# PL_DDR4_SODIMM.net
KiCad netlist of a schematic drawn in Altium Designer
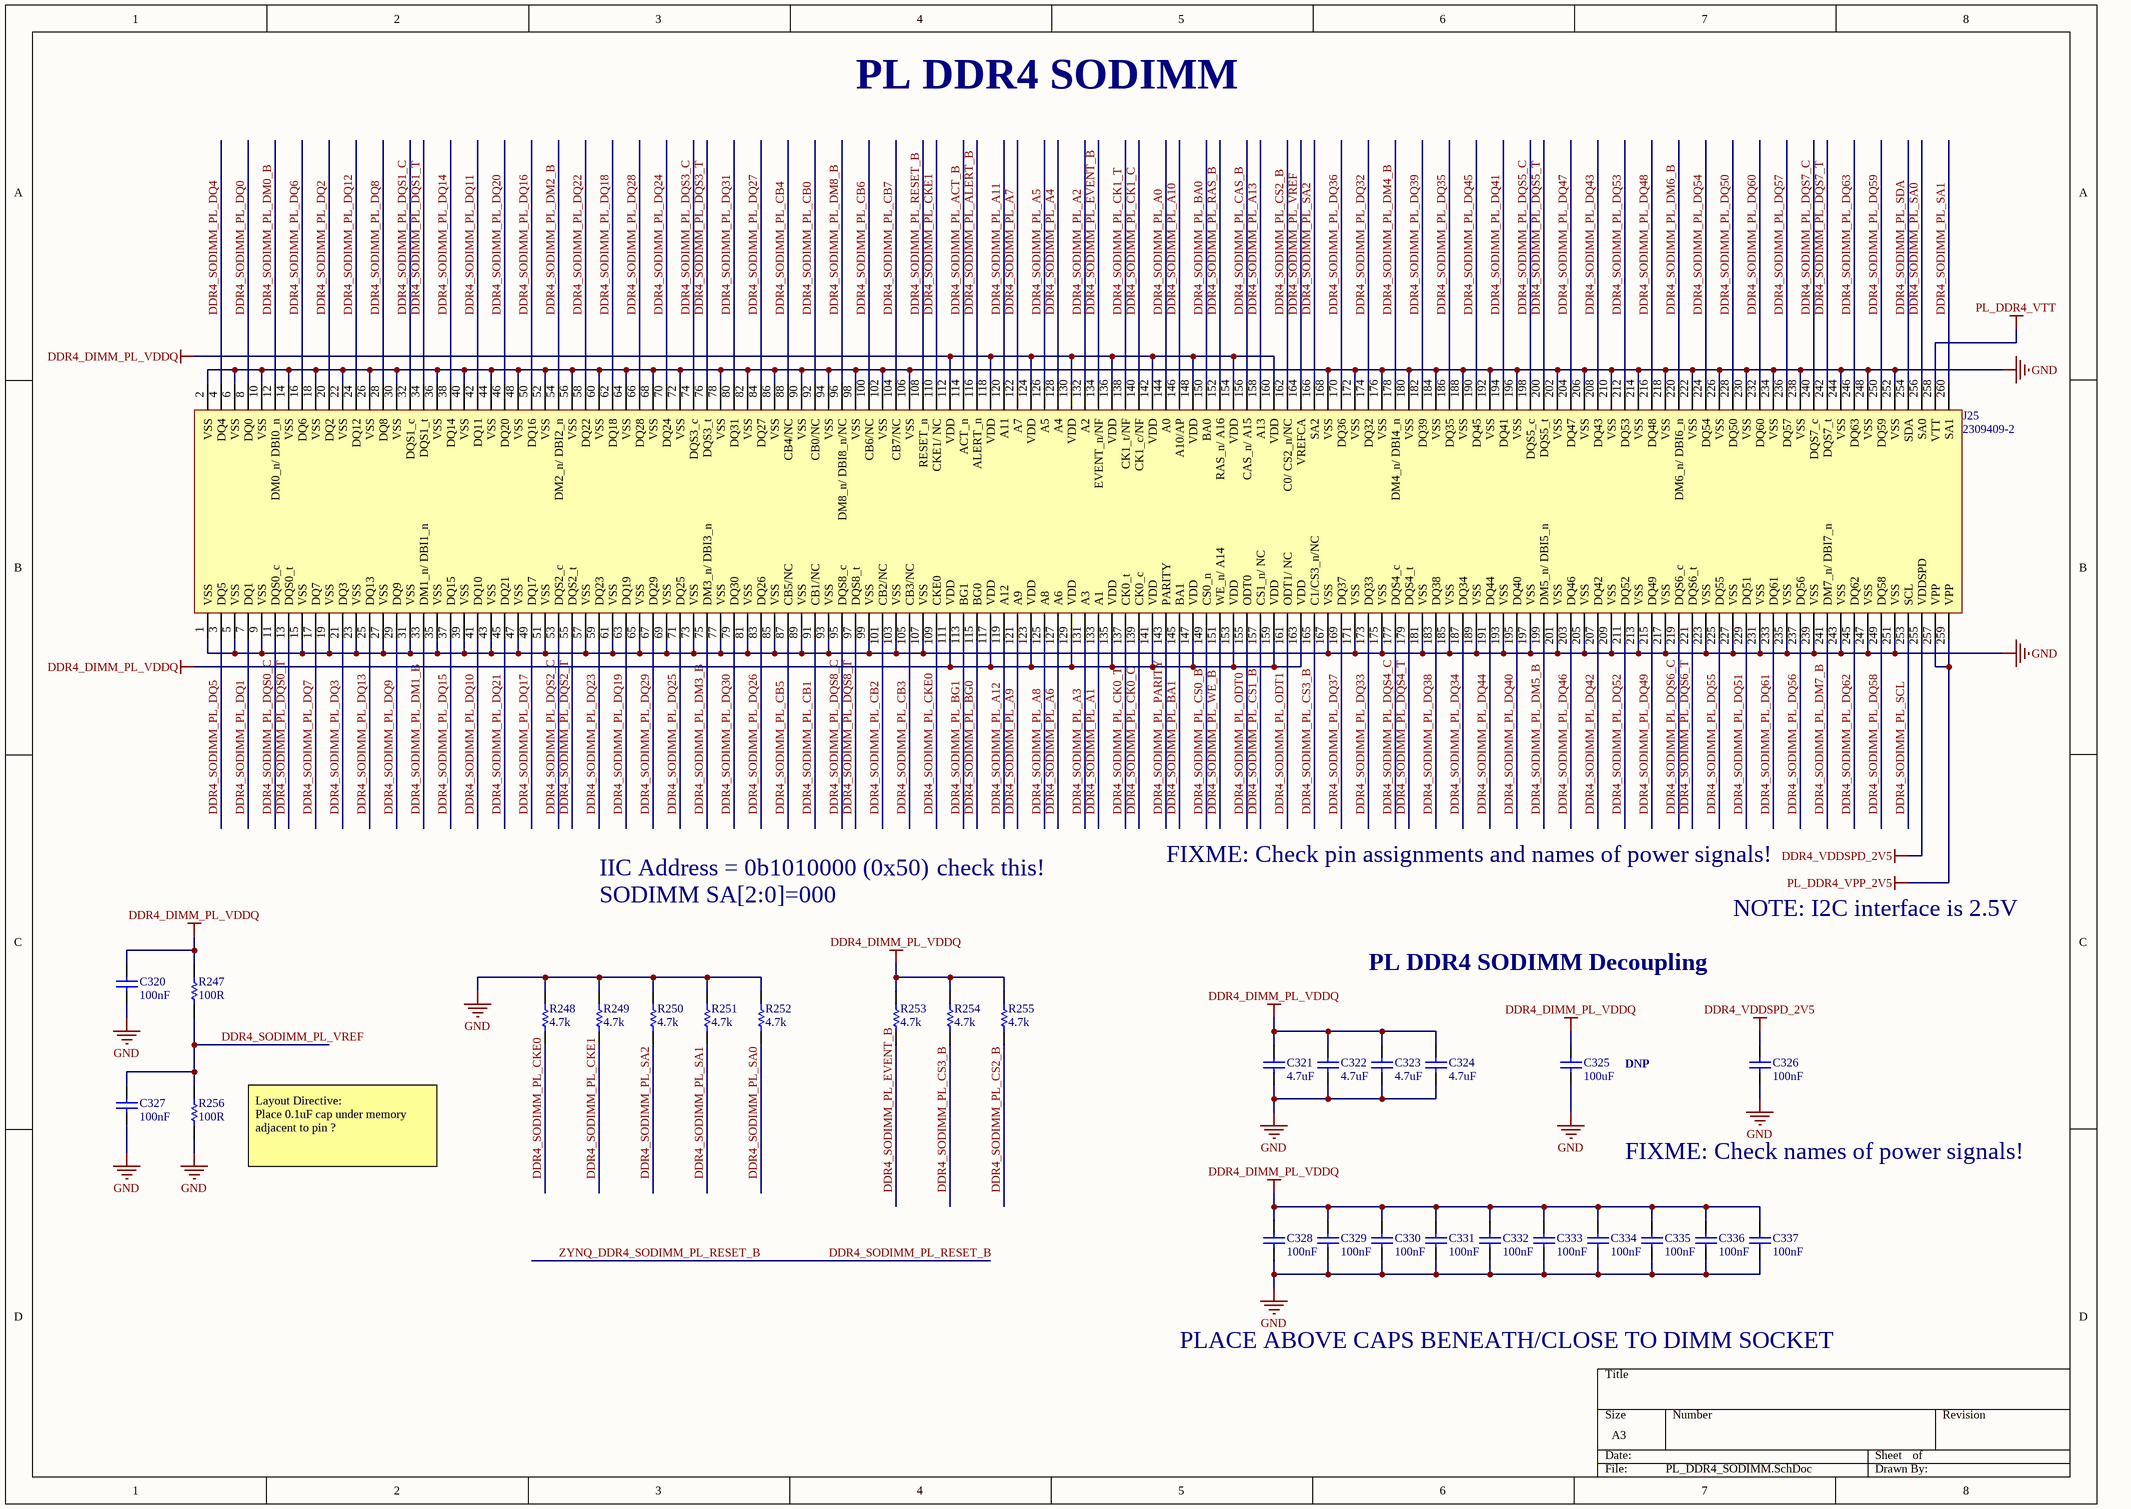
[diagram p0: PL_DDR4_SODIMM.SchDoc]

(export (version "E")
  (design (tool "Eeschema 10.0.6"))
  (components
    (comp (ref "C320")
      (value "100nF")
      (footprint "CAPC1005L_0402")
      (description "CAP CER 0.1UF 25V X7R 0402")
      (fields (field (name "VOLTAGE") "25V") (field (name "TOLERANCE") "10%"))
      (libsource (lib "Ultrascale_SchLib") (part "CAPCER0402X7R100N25V_10T"))
    )
    (comp (ref "C321")
      (value "4.7uF")
      (footprint "CAPC1005L_0402")
      (description "CAP CER 4.7UF 10V X5R 0402")
      (fields (field (name "VOLTAGE") "10V") (field (name "TOLERANCE") "10%"))
      (libsource (lib "Ultrascale_SchLib") (part "CAPCER0402X5R4U710V_10T"))
    )
    (comp (ref "C322")
      (value "4.7uF")
      (footprint "CAPC1005L_0402")
      (description "CAP CER 4.7UF 10V X5R 0402")
      (fields (field (name "VOLTAGE") "10V") (field (name "TOLERANCE") "10%"))
      (libsource (lib "Ultrascale_SchLib") (part "CAPCER0402X5R4U710V_10T"))
    )
    (comp (ref "C323")
      (value "4.7uF")
      (footprint "CAPC1005L_0402")
      (description "CAP CER 4.7UF 10V X5R 0402")
      (fields (field (name "VOLTAGE") "10V") (field (name "TOLERANCE") "10%"))
      (libsource (lib "Ultrascale_SchLib") (part "CAPCER0402X5R4U710V_10T"))
    )
    (comp (ref "C324")
      (value "4.7uF")
      (footprint "CAPC1005L_0402")
      (description "CAP CER 4.7UF 10V X5R 0402")
      (fields (field (name "VOLTAGE") "10V") (field (name "TOLERANCE") "10%"))
      (libsource (lib "Ultrascale_SchLib") (part "CAPCER0402X5R4U710V_10T"))
    )
    (comp (ref "C325")
      (value "100uF")
      (footprint "CAPC3225N_1210")
      (description "CAP CER 100UF 16V X5R 1210")
      (fields (field (name "VOLTAGE") "16V") (field (name "TOLERANCE") "20%"))
      (libsource (lib "Ultrascale_SchLib") (part "CAPCER1210X5R100U16V_20T"))
    )
    (comp (ref "C326")
      (value "100nF")
      (footprint "CAPC1005L_0402")
      (description "CAP CER 0.1UF 25V X7R 0402")
      (fields (field (name "VOLTAGE") "25V") (field (name "TOLERANCE") "10%"))
      (libsource (lib "Ultrascale_SchLib") (part "CAPCER0402X7R100N25V_10T"))
    )
    (comp (ref "C327")
      (value "100nF")
      (footprint "CAPC1005L_0402")
      (description "CAP CER 0.1UF 25V X7R 0402")
      (fields (field (name "VOLTAGE") "25V") (field (name "TOLERANCE") "10%"))
      (libsource (lib "Ultrascale_SchLib") (part "CAPCER0402X7R100N25V_10T"))
    )
    (comp (ref "C328")
      (value "100nF")
      (footprint "CAPC1005L_0402")
      (description "CAP CER 0.1UF 25V X7R 0402")
      (fields (field (name "VOLTAGE") "25V") (field (name "TOLERANCE") "10%"))
      (libsource (lib "Ultrascale_SchLib") (part "CAPCER0402X7R100N25V_10T"))
    )
    (comp (ref "C329")
      (value "100nF")
      (footprint "CAPC1005L_0402")
      (description "CAP CER 0.1UF 25V X7R 0402")
      (fields (field (name "VOLTAGE") "25V") (field (name "TOLERANCE") "10%"))
      (libsource (lib "Ultrascale_SchLib") (part "CAPCER0402X7R100N25V_10T"))
    )
    (comp (ref "C330")
      (value "100nF")
      (footprint "CAPC1005L_0402")
      (description "CAP CER 0.1UF 25V X7R 0402")
      (fields (field (name "VOLTAGE") "25V") (field (name "TOLERANCE") "10%"))
      (libsource (lib "Ultrascale_SchLib") (part "CAPCER0402X7R100N25V_10T"))
    )
    (comp (ref "C331")
      (value "100nF")
      (footprint "CAPC1005L_0402")
      (description "CAP CER 0.1UF 25V X7R 0402")
      (fields (field (name "VOLTAGE") "25V") (field (name "TOLERANCE") "10%"))
      (libsource (lib "Ultrascale_SchLib") (part "CAPCER0402X7R100N25V_10T"))
    )
    (comp (ref "C332")
      (value "100nF")
      (footprint "CAPC1005L_0402")
      (description "CAP CER 0.1UF 25V X7R 0402")
      (fields (field (name "VOLTAGE") "25V") (field (name "TOLERANCE") "10%"))
      (libsource (lib "Ultrascale_SchLib") (part "CAPCER0402X7R100N25V_10T"))
    )
    (comp (ref "C333")
      (value "100nF")
      (footprint "CAPC1005L_0402")
      (description "CAP CER 0.1UF 25V X7R 0402")
      (fields (field (name "VOLTAGE") "25V") (field (name "TOLERANCE") "10%"))
      (libsource (lib "Ultrascale_SchLib") (part "CAPCER0402X7R100N25V_10T"))
    )
    (comp (ref "C334")
      (value "100nF")
      (footprint "CAPC1005L_0402")
      (description "CAP CER 0.1UF 25V X7R 0402")
      (fields (field (name "VOLTAGE") "25V") (field (name "TOLERANCE") "10%"))
      (libsource (lib "Ultrascale_SchLib") (part "CAPCER0402X7R100N25V_10T"))
    )
    (comp (ref "C335")
      (value "100nF")
      (footprint "CAPC1005L_0402")
      (description "CAP CER 0.1UF 25V X7R 0402")
      (fields (field (name "VOLTAGE") "25V") (field (name "TOLERANCE") "10%"))
      (libsource (lib "Ultrascale_SchLib") (part "CAPCER0402X7R100N25V_10T"))
    )
    (comp (ref "C336")
      (value "100nF")
      (footprint "CAPC1005L_0402")
      (description "CAP CER 0.1UF 25V X7R 0402")
      (fields (field (name "VOLTAGE") "25V") (field (name "TOLERANCE") "10%"))
      (libsource (lib "Ultrascale_SchLib") (part "CAPCER0402X7R100N25V_10T"))
    )
    (comp (ref "C337")
      (value "100nF")
      (footprint "CAPC1005L_0402")
      (description "CAP CER 0.1UF 25V X7R 0402")
      (fields (field (name "VOLTAGE") "25V") (field (name "TOLERANCE") "10%"))
      (libsource (lib "Ultrascale_SchLib") (part "CAPCER0402X7R100N25V_10T"))
    )
    (comp (ref "J25")
      (value "2309409-2")
      (footprint "DDR4_SODIMM_MATING")
      (description "DDR4 SODIMM 260P 5.2H STD")
      (libsource (lib "Ultrascale_SchLib") (part "2309409-2"))
    )
    (comp (ref "R247")
      (value "100R")
      (footprint "RESC1005L_0402")
      (description "RES SMD 100 OHM 1% 1/10W 0402")
      (fields (field (name "POWER") "1/10W") (field (name "TOLERANCE") "1%"))
      (libsource (lib "Ultrascale_SchLib") (part "RES0402_100R_0W1_1T"))
    )
    (comp (ref "R248")
      (value "4.7k")
      (footprint "RESC1005L_0402")
      (description "RES SMD 4.7K OHM 1% 1/10W 0402")
      (fields (field (name "POWER") "1/10W") (field (name "TOLERANCE") "1%"))
      (libsource (lib "Ultrascale_SchLib") (part "RES0402_4K7_0W1_1T"))
    )
    (comp (ref "R249")
      (value "4.7k")
      (footprint "RESC1005L_0402")
      (description "RES SMD 4.7K OHM 1% 1/10W 0402")
      (fields (field (name "POWER") "1/10W") (field (name "TOLERANCE") "1%"))
      (libsource (lib "Ultrascale_SchLib") (part "RES0402_4K7_0W1_1T"))
    )
    (comp (ref "R250")
      (value "4.7k")
      (footprint "RESC1005L_0402")
      (description "RES SMD 4.7K OHM 1% 1/10W 0402")
      (fields (field (name "POWER") "1/10W") (field (name "TOLERANCE") "1%"))
      (libsource (lib "Ultrascale_SchLib") (part "RES0402_4K7_0W1_1T"))
    )
    (comp (ref "R251")
      (value "4.7k")
      (footprint "RESC1005L_0402")
      (description "RES SMD 4.7K OHM 1% 1/10W 0402")
      (fields (field (name "POWER") "1/10W") (field (name "TOLERANCE") "1%"))
      (libsource (lib "Ultrascale_SchLib") (part "RES0402_4K7_0W1_1T"))
    )
    (comp (ref "R252")
      (value "4.7k")
      (footprint "RESC1005L_0402")
      (description "RES SMD 4.7K OHM 1% 1/10W 0402")
      (fields (field (name "POWER") "1/10W") (field (name "TOLERANCE") "1%"))
      (libsource (lib "Ultrascale_SchLib") (part "RES0402_4K7_0W1_1T"))
    )
    (comp (ref "R253")
      (value "4.7k")
      (footprint "RESC1005L_0402")
      (description "RES SMD 4.7K OHM 1% 1/10W 0402")
      (fields (field (name "POWER") "1/10W") (field (name "TOLERANCE") "1%"))
      (libsource (lib "Ultrascale_SchLib") (part "RES0402_4K7_0W1_1T"))
    )
    (comp (ref "R254")
      (value "4.7k")
      (footprint "RESC1005L_0402")
      (description "RES SMD 4.7K OHM 1% 1/10W 0402")
      (fields (field (name "POWER") "1/10W") (field (name "TOLERANCE") "1%"))
      (libsource (lib "Ultrascale_SchLib") (part "RES0402_4K7_0W1_1T"))
    )
    (comp (ref "R255")
      (value "4.7k")
      (footprint "RESC1005L_0402")
      (description "RES SMD 4.7K OHM 1% 1/10W 0402")
      (fields (field (name "POWER") "1/10W") (field (name "TOLERANCE") "1%"))
      (libsource (lib "Ultrascale_SchLib") (part "RES0402_4K7_0W1_1T"))
    )
    (comp (ref "R256")
      (value "100R")
      (footprint "RESC1005L_0402")
      (description "RES SMD 100 OHM 1% 1/10W 0402")
      (fields (field (name "POWER") "1/10W") (field (name "TOLERANCE") "1%"))
      (libsource (lib "Ultrascale_SchLib") (part "RES0402_100R_0W1_1T"))
    )
  )
  (nets
    (net (code "1") (name "/DDR4_SODIMM_PL_A0") (class "Default")
      (node (ref "J25") (pin "144") (pinfunction "A0_144") (pintype "power_in"))
    )
    (net (code "2") (name "/DDR4_SODIMM_PL_A1") (class "Default")
      (node (ref "J25") (pin "133") (pinfunction "A1_133") (pintype "power_in"))
    )
    (net (code "3") (name "/DDR4_SODIMM_PL_A2") (class "Default")
      (node (ref "J25") (pin "132") (pinfunction "A2_132") (pintype "power_in"))
    )
    (net (code "4") (name "/DDR4_SODIMM_PL_A3") (class "Default")
      (node (ref "J25") (pin "131") (pinfunction "A3_131") (pintype "power_in"))
    )
    (net (code "5") (name "/DDR4_SODIMM_PL_A4") (class "Default")
      (node (ref "J25") (pin "128") (pinfunction "A4_128") (pintype "power_in"))
    )
    (net (code "6") (name "/DDR4_SODIMM_PL_A5") (class "Default")
      (node (ref "J25") (pin "126") (pinfunction "A5_126") (pintype "power_in"))
    )
    (net (code "7") (name "/DDR4_SODIMM_PL_A6") (class "Default")
      (node (ref "J25") (pin "127") (pinfunction "A6_127") (pintype "power_in"))
    )
    (net (code "8") (name "/DDR4_SODIMM_PL_A7") (class "Default")
      (node (ref "J25") (pin "122") (pinfunction "A7_122") (pintype "power_in"))
    )
    (net (code "9") (name "/DDR4_SODIMM_PL_A8") (class "Default")
      (node (ref "J25") (pin "125") (pinfunction "A8_125") (pintype "power_in"))
    )
    (net (code "10") (name "/DDR4_SODIMM_PL_A9") (class "Default")
      (node (ref "J25") (pin "121") (pinfunction "A9_121") (pintype "power_in"))
    )
    (net (code "11") (name "/DDR4_SODIMM_PL_A10") (class "Default")
      (node (ref "J25") (pin "146") (pinfunction "A10/AP_146") (pintype "power_in"))
    )
    (net (code "12") (name "/DDR4_SODIMM_PL_A11") (class "Default")
      (node (ref "J25") (pin "120") (pinfunction "A11_120") (pintype "power_in"))
    )
    (net (code "13") (name "/DDR4_SODIMM_PL_A12") (class "Default")
      (node (ref "J25") (pin "119") (pinfunction "A12_119") (pintype "power_in"))
    )
    (net (code "14") (name "/DDR4_SODIMM_PL_A13") (class "Default")
      (node (ref "J25") (pin "158") (pinfunction "A13_158") (pintype "power_in"))
    )
    (net (code "15") (name "/DDR4_SODIMM_PL_ACT_B") (class "Default")
      (node (ref "J25") (pin "114") (pinfunction "ACT_n_114") (pintype "power_in"))
    )
    (net (code "16") (name "/DDR4_SODIMM_PL_ALERT_B") (class "Default")
      (node (ref "J25") (pin "116") (pinfunction "ALERT_n_116") (pintype "power_in"))
    )
    (net (code "17") (name "/DDR4_SODIMM_PL_BA0") (class "Default")
      (node (ref "J25") (pin "150") (pinfunction "BA0_150") (pintype "power_in"))
    )
    (net (code "18") (name "/DDR4_SODIMM_PL_BA1") (class "Default")
      (node (ref "J25") (pin "145") (pinfunction "BA1_145") (pintype "power_in"))
    )
    (net (code "19") (name "/DDR4_SODIMM_PL_BG0") (class "Default")
      (node (ref "J25") (pin "115") (pinfunction "BG0_115") (pintype "power_in"))
    )
    (net (code "20") (name "/DDR4_SODIMM_PL_BG1") (class "Default")
      (node (ref "J25") (pin "113") (pinfunction "BG1_113") (pintype "power_in"))
    )
    (net (code "21") (name "/DDR4_SODIMM_PL_CAS_B") (class "Default")
      (node (ref "J25") (pin "156") (pinfunction "CAS_n/_A15_156") (pintype "power_in"))
    )
    (net (code "22") (name "/DDR4_SODIMM_PL_CB0") (class "Default")
      (node (ref "J25") (pin "92") (pinfunction "CB0/NC_92") (pintype "power_in"))
    )
    (net (code "23") (name "/DDR4_SODIMM_PL_CB1") (class "Default")
      (node (ref "J25") (pin "91") (pinfunction "CB1/NC_91") (pintype "power_in"))
    )
    (net (code "24") (name "/DDR4_SODIMM_PL_CB2") (class "Default")
      (node (ref "J25") (pin "101") (pinfunction "CB2/NC_101") (pintype "power_in"))
    )
    (net (code "25") (name "/DDR4_SODIMM_PL_CB3") (class "Default")
      (node (ref "J25") (pin "105") (pinfunction "CB3/NC_105") (pintype "power_in"))
    )
    (net (code "26") (name "/DDR4_SODIMM_PL_CB4") (class "Default")
      (node (ref "J25") (pin "88") (pinfunction "CB4/NC_88") (pintype "power_in"))
    )
    (net (code "27") (name "/DDR4_SODIMM_PL_CB5") (class "Default")
      (node (ref "J25") (pin "87") (pinfunction "CB5/NC_87") (pintype "power_in"))
    )
    (net (code "28") (name "/DDR4_SODIMM_PL_CB6") (class "Default")
      (node (ref "J25") (pin "100") (pinfunction "CB6/NC_100") (pintype "power_in"))
    )
    (net (code "29") (name "/DDR4_SODIMM_PL_CB7") (class "Default")
      (node (ref "J25") (pin "104") (pinfunction "CB7/NC_104") (pintype "power_in"))
    )
    (net (code "30") (name "/DDR4_SODIMM_PL_CK0_C") (class "Default")
      (node (ref "J25") (pin "139") (pinfunction "CK0_c_139") (pintype "power_in"))
    )
    (net (code "31") (name "/DDR4_SODIMM_PL_CK0_T") (class "Default")
      (node (ref "J25") (pin "137") (pinfunction "CK0_t_137") (pintype "power_in"))
    )
    (net (code "32") (name "/DDR4_SODIMM_PL_CK1_C") (class "Default")
      (node (ref "J25") (pin "140") (pinfunction "CK1_c/NF_140") (pintype "power_in"))
    )
    (net (code "33") (name "/DDR4_SODIMM_PL_CK1_T") (class "Default")
      (node (ref "J25") (pin "138") (pinfunction "CK1_t/NF_138") (pintype "power_in"))
    )
    (net (code "34") (name "/DDR4_SODIMM_PL_CKE0") (class "Default")
      (node (ref "J25") (pin "109") (pinfunction "CKE0_109") (pintype "power_in"))
      (node (ref "R248") (pin "1") (pinfunction "1_1") (pintype "passive"))
    )
    (net (code "35") (name "/DDR4_SODIMM_PL_CKE1") (class "Default")
      (node (ref "J25") (pin "110") (pinfunction "CKE1/_NC_110") (pintype "power_in"))
      (node (ref "R249") (pin "1") (pinfunction "1_1") (pintype "passive"))
    )
    (net (code "36") (name "/DDR4_SODIMM_PL_CS0_B") (class "Default")
      (node (ref "J25") (pin "149") (pinfunction "CS0_n_149") (pintype "power_in"))
    )
    (net (code "37") (name "/DDR4_SODIMM_PL_CS1_B") (class "Default")
      (node (ref "J25") (pin "157") (pinfunction "CS1_n/_NC_157") (pintype "power_in"))
    )
    (net (code "38") (name "/DDR4_SODIMM_PL_CS2_B") (class "Default")
      (node (ref "J25") (pin "162") (pinfunction "C0/_CS2_n/NC_162") (pintype "power_in"))
      (node (ref "R255") (pin "1") (pinfunction "1_1") (pintype "passive"))
    )
    (net (code "39") (name "/DDR4_SODIMM_PL_CS3_B") (class "Default")
      (node (ref "J25") (pin "165") (pinfunction "C1/CS3_n/NC_165") (pintype "power_in"))
      (node (ref "R254") (pin "1") (pinfunction "1_1") (pintype "passive"))
    )
    (net (code "40") (name "/DDR4_SODIMM_PL_DM0_B") (class "Default")
      (node (ref "J25") (pin "12") (pinfunction "DM0_n/_DBI0_n_12") (pintype "power_in"))
    )
    (net (code "41") (name "/DDR4_SODIMM_PL_DM1_B") (class "Default")
      (node (ref "J25") (pin "33") (pinfunction "DM1_n/_DBI1_n_33") (pintype "power_in"))
    )
    (net (code "42") (name "/DDR4_SODIMM_PL_DM2_B") (class "Default")
      (node (ref "J25") (pin "54") (pinfunction "DM2_n/_DBI2_n_54") (pintype "power_in"))
    )
    (net (code "43") (name "/DDR4_SODIMM_PL_DM3_B") (class "Default")
      (node (ref "J25") (pin "75") (pinfunction "DM3_n/_DBI3_n_75") (pintype "power_in"))
    )
    (net (code "44") (name "/DDR4_SODIMM_PL_DM4_B") (class "Default")
      (node (ref "J25") (pin "178") (pinfunction "DM4_n/_DBI4_n_178") (pintype "power_in"))
    )
    (net (code "45") (name "/DDR4_SODIMM_PL_DM5_B") (class "Default")
      (node (ref "J25") (pin "199") (pinfunction "DM5_n/_DBI5_n_199") (pintype "power_in"))
    )
    (net (code "46") (name "/DDR4_SODIMM_PL_DM6_B") (class "Default")
      (node (ref "J25") (pin "220") (pinfunction "DM6_n/_DBI6_n_220") (pintype "power_in"))
    )
    (net (code "47") (name "/DDR4_SODIMM_PL_DM7_B") (class "Default")
      (node (ref "J25") (pin "241") (pinfunction "DM7_n/_DBI7_n_241") (pintype "power_in"))
    )
    (net (code "48") (name "/DDR4_SODIMM_PL_DM8_B") (class "Default")
      (node (ref "J25") (pin "96") (pinfunction "DM8_n/_DBI8_n/NC_96") (pintype "power_in"))
    )
    (net (code "49") (name "/DDR4_SODIMM_PL_DQ0") (class "Default")
      (node (ref "J25") (pin "8") (pinfunction "DQ0_8") (pintype "power_in"))
    )
    (net (code "50") (name "/DDR4_SODIMM_PL_DQ1") (class "Default")
      (node (ref "J25") (pin "7") (pinfunction "DQ1_7") (pintype "power_in"))
    )
    (net (code "51") (name "/DDR4_SODIMM_PL_DQ2") (class "Default")
      (node (ref "J25") (pin "20") (pinfunction "DQ2_20") (pintype "power_in"))
    )
    (net (code "52") (name "/DDR4_SODIMM_PL_DQ3") (class "Default")
      (node (ref "J25") (pin "21") (pinfunction "DQ3_21") (pintype "power_in"))
    )
    (net (code "53") (name "/DDR4_SODIMM_PL_DQ4") (class "Default")
      (node (ref "J25") (pin "4") (pinfunction "DQ4_4") (pintype "power_in"))
    )
    (net (code "54") (name "/DDR4_SODIMM_PL_DQ5") (class "Default")
      (node (ref "J25") (pin "3") (pinfunction "DQ5_3") (pintype "power_in"))
    )
    (net (code "55") (name "/DDR4_SODIMM_PL_DQ6") (class "Default")
      (node (ref "J25") (pin "16") (pinfunction "DQ6_16") (pintype "power_in"))
    )
    (net (code "56") (name "/DDR4_SODIMM_PL_DQ7") (class "Default")
      (node (ref "J25") (pin "17") (pinfunction "DQ7_17") (pintype "power_in"))
    )
    (net (code "57") (name "/DDR4_SODIMM_PL_DQ8") (class "Default")
      (node (ref "J25") (pin "28") (pinfunction "DQ8_28") (pintype "power_in"))
    )
    (net (code "58") (name "/DDR4_SODIMM_PL_DQ9") (class "Default")
      (node (ref "J25") (pin "29") (pinfunction "DQ9_29") (pintype "power_in"))
    )
    (net (code "59") (name "/DDR4_SODIMM_PL_DQ10") (class "Default")
      (node (ref "J25") (pin "41") (pinfunction "DQ10_41") (pintype "power_in"))
    )
    (net (code "60") (name "/DDR4_SODIMM_PL_DQ11") (class "Default")
      (node (ref "J25") (pin "42") (pinfunction "DQ11_42") (pintype "power_in"))
    )
    (net (code "61") (name "/DDR4_SODIMM_PL_DQ12") (class "Default")
      (node (ref "J25") (pin "24") (pinfunction "DQ12_24") (pintype "power_in"))
    )
    (net (code "62") (name "/DDR4_SODIMM_PL_DQ13") (class "Default")
      (node (ref "J25") (pin "25") (pinfunction "DQ13_25") (pintype "power_in"))
    )
    (net (code "63") (name "/DDR4_SODIMM_PL_DQ14") (class "Default")
      (node (ref "J25") (pin "38") (pinfunction "DQ14_38") (pintype "power_in"))
    )
    (net (code "64") (name "/DDR4_SODIMM_PL_DQ15") (class "Default")
      (node (ref "J25") (pin "37") (pinfunction "DQ15_37") (pintype "power_in"))
    )
    (net (code "65") (name "/DDR4_SODIMM_PL_DQ16") (class "Default")
      (node (ref "J25") (pin "50") (pinfunction "DQ16_50") (pintype "power_in"))
    )
    (net (code "66") (name "/DDR4_SODIMM_PL_DQ17") (class "Default")
      (node (ref "J25") (pin "49") (pinfunction "DQ17_49") (pintype "power_in"))
    )
    (net (code "67") (name "/DDR4_SODIMM_PL_DQ18") (class "Default")
      (node (ref "J25") (pin "62") (pinfunction "DQ18_62") (pintype "power_in"))
    )
    (net (code "68") (name "/DDR4_SODIMM_PL_DQ19") (class "Default")
      (node (ref "J25") (pin "63") (pinfunction "DQ19_63") (pintype "power_in"))
    )
    (net (code "69") (name "/DDR4_SODIMM_PL_DQ20") (class "Default")
      (node (ref "J25") (pin "46") (pinfunction "DQ20_46") (pintype "power_in"))
    )
    (net (code "70") (name "/DDR4_SODIMM_PL_DQ21") (class "Default")
      (node (ref "J25") (pin "45") (pinfunction "DQ21_45") (pintype "power_in"))
    )
    (net (code "71") (name "/DDR4_SODIMM_PL_DQ22") (class "Default")
      (node (ref "J25") (pin "58") (pinfunction "DQ22_58") (pintype "power_in"))
    )
    (net (code "72") (name "/DDR4_SODIMM_PL_DQ23") (class "Default")
      (node (ref "J25") (pin "59") (pinfunction "DQ23_59") (pintype "power_in"))
    )
    (net (code "73") (name "/DDR4_SODIMM_PL_DQ24") (class "Default")
      (node (ref "J25") (pin "70") (pinfunction "DQ24_70") (pintype "power_in"))
    )
    (net (code "74") (name "/DDR4_SODIMM_PL_DQ25") (class "Default")
      (node (ref "J25") (pin "71") (pinfunction "DQ25_71") (pintype "power_in"))
    )
    (net (code "75") (name "/DDR4_SODIMM_PL_DQ26") (class "Default")
      (node (ref "J25") (pin "83") (pinfunction "DQ26_83") (pintype "power_in"))
    )
    (net (code "76") (name "/DDR4_SODIMM_PL_DQ27") (class "Default")
      (node (ref "J25") (pin "84") (pinfunction "DQ27_84") (pintype "power_in"))
    )
    (net (code "77") (name "/DDR4_SODIMM_PL_DQ28") (class "Default")
      (node (ref "J25") (pin "66") (pinfunction "DQ28_66") (pintype "power_in"))
    )
    (net (code "78") (name "/DDR4_SODIMM_PL_DQ29") (class "Default")
      (node (ref "J25") (pin "67") (pinfunction "DQ29_67") (pintype "power_in"))
    )
    (net (code "79") (name "/DDR4_SODIMM_PL_DQ30") (class "Default")
      (node (ref "J25") (pin "79") (pinfunction "DQ30_79") (pintype "power_in"))
    )
    (net (code "80") (name "/DDR4_SODIMM_PL_DQ31") (class "Default")
      (node (ref "J25") (pin "80") (pinfunction "DQ31_80") (pintype "power_in"))
    )
    (net (code "81") (name "/DDR4_SODIMM_PL_DQ32") (class "Default")
      (node (ref "J25") (pin "174") (pinfunction "DQ32_174") (pintype "power_in"))
    )
    (net (code "82") (name "/DDR4_SODIMM_PL_DQ33") (class "Default")
      (node (ref "J25") (pin "173") (pinfunction "DQ33_173") (pintype "power_in"))
    )
    (net (code "83") (name "/DDR4_SODIMM_PL_DQ34") (class "Default")
      (node (ref "J25") (pin "187") (pinfunction "DQ34_187") (pintype "power_in"))
    )
    (net (code "84") (name "/DDR4_SODIMM_PL_DQ35") (class "Default")
      (node (ref "J25") (pin "186") (pinfunction "DQ35_186") (pintype "power_in"))
    )
    (net (code "85") (name "/DDR4_SODIMM_PL_DQ36") (class "Default")
      (node (ref "J25") (pin "170") (pinfunction "DQ36_170") (pintype "power_in"))
    )
    (net (code "86") (name "/DDR4_SODIMM_PL_DQ37") (class "Default")
      (node (ref "J25") (pin "169") (pinfunction "DQ37_169") (pintype "power_in"))
    )
    (net (code "87") (name "/DDR4_SODIMM_PL_DQ38") (class "Default")
      (node (ref "J25") (pin "183") (pinfunction "DQ38_183") (pintype "power_in"))
    )
    (net (code "88") (name "/DDR4_SODIMM_PL_DQ39") (class "Default")
      (node (ref "J25") (pin "182") (pinfunction "DQ39_182") (pintype "power_in"))
    )
    (net (code "89") (name "/DDR4_SODIMM_PL_DQ40") (class "Default")
      (node (ref "J25") (pin "195") (pinfunction "DQ40_195") (pintype "power_in"))
    )
    (net (code "90") (name "/DDR4_SODIMM_PL_DQ41") (class "Default")
      (node (ref "J25") (pin "194") (pinfunction "DQ41_194") (pintype "power_in"))
    )
    (net (code "91") (name "/DDR4_SODIMM_PL_DQ42") (class "Default")
      (node (ref "J25") (pin "207") (pinfunction "DQ42_207") (pintype "power_in"))
    )
    (net (code "92") (name "/DDR4_SODIMM_PL_DQ43") (class "Default")
      (node (ref "J25") (pin "208") (pinfunction "DQ43_208") (pintype "power_in"))
    )
    (net (code "93") (name "/DDR4_SODIMM_PL_DQ44") (class "Default")
      (node (ref "J25") (pin "191") (pinfunction "DQ44_191") (pintype "power_in"))
    )
    (net (code "94") (name "/DDR4_SODIMM_PL_DQ45") (class "Default")
      (node (ref "J25") (pin "190") (pinfunction "DQ45_190") (pintype "power_in"))
    )
    (net (code "95") (name "/DDR4_SODIMM_PL_DQ46") (class "Default")
      (node (ref "J25") (pin "203") (pinfunction "DQ46_203") (pintype "power_in"))
    )
    (net (code "96") (name "/DDR4_SODIMM_PL_DQ47") (class "Default")
      (node (ref "J25") (pin "204") (pinfunction "DQ47_204") (pintype "power_in"))
    )
    (net (code "97") (name "/DDR4_SODIMM_PL_DQ48") (class "Default")
      (node (ref "J25") (pin "216") (pinfunction "DQ48_216") (pintype "power_in"))
    )
    (net (code "98") (name "/DDR4_SODIMM_PL_DQ49") (class "Default")
      (node (ref "J25") (pin "215") (pinfunction "DQ49_215") (pintype "power_in"))
    )
    (net (code "99") (name "/DDR4_SODIMM_PL_DQ50") (class "Default")
      (node (ref "J25") (pin "228") (pinfunction "DQ50_228") (pintype "power_in"))
    )
    (net (code "100") (name "/DDR4_SODIMM_PL_DQ51") (class "Default")
      (node (ref "J25") (pin "229") (pinfunction "DQ51_229") (pintype "power_in"))
    )
    (net (code "101") (name "/DDR4_SODIMM_PL_DQ52") (class "Default")
      (node (ref "J25") (pin "211") (pinfunction "DQ52_211") (pintype "power_in"))
    )
    (net (code "102") (name "/DDR4_SODIMM_PL_DQ53") (class "Default")
      (node (ref "J25") (pin "212") (pinfunction "DQ53_212") (pintype "power_in"))
    )
    (net (code "103") (name "/DDR4_SODIMM_PL_DQ54") (class "Default")
      (node (ref "J25") (pin "224") (pinfunction "DQ54_224") (pintype "power_in"))
    )
    (net (code "104") (name "/DDR4_SODIMM_PL_DQ55") (class "Default")
      (node (ref "J25") (pin "225") (pinfunction "DQ55_225") (pintype "power_in"))
    )
    (net (code "105") (name "/DDR4_SODIMM_PL_DQ56") (class "Default")
      (node (ref "J25") (pin "237") (pinfunction "DQ56_237") (pintype "power_in"))
    )
    (net (code "106") (name "/DDR4_SODIMM_PL_DQ57") (class "Default")
      (node (ref "J25") (pin "236") (pinfunction "DQ57_236") (pintype "power_in"))
    )
    (net (code "107") (name "/DDR4_SODIMM_PL_DQ58") (class "Default")
      (node (ref "J25") (pin "249") (pinfunction "DQ58_249") (pintype "power_in"))
    )
    (net (code "108") (name "/DDR4_SODIMM_PL_DQ59") (class "Default")
      (node (ref "J25") (pin "250") (pinfunction "DQ59_250") (pintype "power_in"))
    )
    (net (code "109") (name "/DDR4_SODIMM_PL_DQ60") (class "Default")
      (node (ref "J25") (pin "232") (pinfunction "DQ60_232") (pintype "power_in"))
    )
    (net (code "110") (name "/DDR4_SODIMM_PL_DQ61") (class "Default")
      (node (ref "J25") (pin "233") (pinfunction "DQ61_233") (pintype "power_in"))
    )
    (net (code "111") (name "/DDR4_SODIMM_PL_DQ62") (class "Default")
      (node (ref "J25") (pin "245") (pinfunction "DQ62_245") (pintype "power_in"))
    )
    (net (code "112") (name "/DDR4_SODIMM_PL_DQ63") (class "Default")
      (node (ref "J25") (pin "246") (pinfunction "DQ63_246") (pintype "power_in"))
    )
    (net (code "113") (name "/DDR4_SODIMM_PL_DQS0_C") (class "Default")
      (node (ref "J25") (pin "11") (pinfunction "DQS0_c_11") (pintype "power_in"))
    )
    (net (code "114") (name "/DDR4_SODIMM_PL_DQS0_T") (class "Default")
      (node (ref "J25") (pin "13") (pinfunction "DQS0_t_13") (pintype "power_in"))
    )
    (net (code "115") (name "/DDR4_SODIMM_PL_DQS1_C") (class "Default")
      (node (ref "J25") (pin "32") (pinfunction "DQS1_c_32") (pintype "power_in"))
    )
    (net (code "116") (name "/DDR4_SODIMM_PL_DQS1_T") (class "Default")
      (node (ref "J25") (pin "34") (pinfunction "DQS1_t_34") (pintype "power_in"))
    )
    (net (code "117") (name "/DDR4_SODIMM_PL_DQS2_C") (class "Default")
      (node (ref "J25") (pin "53") (pinfunction "DQS2_c_53") (pintype "power_in"))
    )
    (net (code "118") (name "/DDR4_SODIMM_PL_DQS2_T") (class "Default")
      (node (ref "J25") (pin "55") (pinfunction "DQS2_t_55") (pintype "power_in"))
    )
    (net (code "119") (name "/DDR4_SODIMM_PL_DQS3_C") (class "Default")
      (node (ref "J25") (pin "74") (pinfunction "DQS3_c_74") (pintype "power_in"))
    )
    (net (code "120") (name "/DDR4_SODIMM_PL_DQS3_T") (class "Default")
      (node (ref "J25") (pin "76") (pinfunction "DQS3_t_76") (pintype "power_in"))
    )
    (net (code "121") (name "/DDR4_SODIMM_PL_DQS4_C") (class "Default")
      (node (ref "J25") (pin "177") (pinfunction "DQS4_c_177") (pintype "power_in"))
    )
    (net (code "122") (name "/DDR4_SODIMM_PL_DQS4_T") (class "Default")
      (node (ref "J25") (pin "179") (pinfunction "DQS4_t_179") (pintype "power_in"))
    )
    (net (code "123") (name "/DDR4_SODIMM_PL_DQS5_C") (class "Default")
      (node (ref "J25") (pin "198") (pinfunction "DQS5_c_198") (pintype "power_in"))
    )
    (net (code "124") (name "/DDR4_SODIMM_PL_DQS5_T") (class "Default")
      (node (ref "J25") (pin "200") (pinfunction "DQS5_t_200") (pintype "power_in"))
    )
    (net (code "125") (name "/DDR4_SODIMM_PL_DQS6_C") (class "Default")
      (node (ref "J25") (pin "219") (pinfunction "DQS6_c_219") (pintype "power_in"))
    )
    (net (code "126") (name "/DDR4_SODIMM_PL_DQS6_T") (class "Default")
      (node (ref "J25") (pin "221") (pinfunction "DQS6_t_221") (pintype "power_in"))
    )
    (net (code "127") (name "/DDR4_SODIMM_PL_DQS7_C") (class "Default")
      (node (ref "J25") (pin "240") (pinfunction "DQS7_c_240") (pintype "power_in"))
    )
    (net (code "128") (name "/DDR4_SODIMM_PL_DQS7_T") (class "Default")
      (node (ref "J25") (pin "242") (pinfunction "DQS7_t_242") (pintype "power_in"))
    )
    (net (code "129") (name "/DDR4_SODIMM_PL_DQS8_C") (class "Default")
      (node (ref "J25") (pin "95") (pinfunction "DQS8_c_95") (pintype "power_in"))
    )
    (net (code "130") (name "/DDR4_SODIMM_PL_DQS8_T") (class "Default")
      (node (ref "J25") (pin "97") (pinfunction "DQS8_t_97") (pintype "power_in"))
    )
    (net (code "131") (name "/DDR4_SODIMM_PL_EVENT_B") (class "Default")
      (node (ref "J25") (pin "134") (pinfunction "EVENT_n/NF_134") (pintype "power_in"))
      (node (ref "R253") (pin "1") (pinfunction "1_1") (pintype "passive"))
    )
    (net (code "132") (name "/DDR4_SODIMM_PL_ODT0") (class "Default")
      (node (ref "J25") (pin "155") (pinfunction "ODT0_155") (pintype "power_in"))
    )
    (net (code "133") (name "/DDR4_SODIMM_PL_ODT1") (class "Default")
      (node (ref "J25") (pin "161") (pinfunction "ODT1/_NC_161") (pintype "power_in"))
    )
    (net (code "134") (name "/DDR4_SODIMM_PL_PARITY") (class "Default")
      (node (ref "J25") (pin "143") (pinfunction "PARITY_143") (pintype "power_in"))
    )
    (net (code "135") (name "/DDR4_SODIMM_PL_RAS_B") (class "Default")
      (node (ref "J25") (pin "152") (pinfunction "RAS_n/_A16_152") (pintype "power_in"))
    )
    (net (code "136") (name "/DDR4_SODIMM_PL_RESET_B") (class "Default")
      (node (ref "J25") (pin "108") (pinfunction "RESET_n_108") (pintype "power_in"))
    )
    (net (code "137") (name "/DDR4_SODIMM_PL_SA0") (class "Default")
      (node (ref "J25") (pin "256") (pinfunction "SA0_256") (pintype "power_in"))
      (node (ref "R252") (pin "1") (pinfunction "1_1") (pintype "passive"))
    )
    (net (code "138") (name "/DDR4_SODIMM_PL_SA1") (class "Default")
      (node (ref "J25") (pin "260") (pinfunction "SA1_260") (pintype "power_in"))
      (node (ref "R251") (pin "1") (pinfunction "1_1") (pintype "passive"))
    )
    (net (code "139") (name "/DDR4_SODIMM_PL_SA2") (class "Default")
      (node (ref "J25") (pin "166") (pinfunction "SA2_166") (pintype "power_in"))
      (node (ref "R250") (pin "1") (pinfunction "1_1") (pintype "passive"))
    )
    (net (code "140") (name "/DDR4_SODIMM_PL_SCL") (class "Default")
      (node (ref "J25") (pin "253") (pinfunction "SCL_253") (pintype "power_in"))
    )
    (net (code "141") (name "/DDR4_SODIMM_PL_SDA") (class "Default")
      (node (ref "J25") (pin "254") (pinfunction "SDA_254") (pintype "power_in"))
    )
    (net (code "142") (name "/DDR4_SODIMM_PL_VREF") (class "Default")
      (node (ref "C327") (pin "2") (pinfunction "2_2") (pintype "passive"))
      (node (ref "J25") (pin "164") (pinfunction "VREFCA_164") (pintype "power_in"))
      (node (ref "R247") (pin "1") (pinfunction "1_1") (pintype "passive"))
      (node (ref "R256") (pin "2") (pinfunction "2_2") (pintype "passive"))
    )
    (net (code "143") (name "/DDR4_SODIMM_PL_WE_B") (class "Default")
      (node (ref "J25") (pin "151") (pinfunction "WE_n/_A14_151") (pintype "power_in"))
    )
    (net (code "144") (name "DDR4_DIMM_PL_VDDQ") (class "Default")
      (node (ref "C320") (pin "2") (pinfunction "2_2") (pintype "passive"))
      (node (ref "C321") (pin "2") (pinfunction "2_2") (pintype "passive"))
      (node (ref "C322") (pin "2") (pinfunction "2_2") (pintype "passive"))
      (node (ref "C323") (pin "2") (pinfunction "2_2") (pintype "passive"))
      (node (ref "C324") (pin "2") (pinfunction "2_2") (pintype "passive"))
      (node (ref "C325") (pin "2") (pinfunction "2_2") (pintype "passive"))
      (node (ref "C328") (pin "2") (pinfunction "2_2") (pintype "passive"))
      (node (ref "C329") (pin "2") (pinfunction "2_2") (pintype "passive"))
      (node (ref "C330") (pin "2") (pinfunction "2_2") (pintype "passive"))
      (node (ref "C331") (pin "2") (pinfunction "2_2") (pintype "passive"))
      (node (ref "C332") (pin "2") (pinfunction "2_2") (pintype "passive"))
      (node (ref "C333") (pin "2") (pinfunction "2_2") (pintype "passive"))
      (node (ref "C334") (pin "2") (pinfunction "2_2") (pintype "passive"))
      (node (ref "C335") (pin "2") (pinfunction "2_2") (pintype "passive"))
      (node (ref "C336") (pin "2") (pinfunction "2_2") (pintype "passive"))
      (node (ref "C337") (pin "2") (pinfunction "2_2") (pintype "passive"))
      (node (ref "J25") (pin "111") (pinfunction "VDD_111") (pintype "power_in"))
      (node (ref "J25") (pin "112") (pinfunction "VDD_112") (pintype "power_in"))
      (node (ref "J25") (pin "117") (pinfunction "VDD_117") (pintype "power_in"))
      (node (ref "J25") (pin "118") (pinfunction "VDD_118") (pintype "power_in"))
      (node (ref "J25") (pin "123") (pinfunction "VDD_123") (pintype "power_in"))
      (node (ref "J25") (pin "124") (pinfunction "VDD_124") (pintype "power_in"))
      (node (ref "J25") (pin "129") (pinfunction "VDD_129") (pintype "power_in"))
      (node (ref "J25") (pin "130") (pinfunction "VDD_130") (pintype "power_in"))
      (node (ref "J25") (pin "135") (pinfunction "VDD_135") (pintype "power_in"))
      (node (ref "J25") (pin "136") (pinfunction "VDD_136") (pintype "power_in"))
      (node (ref "J25") (pin "141") (pinfunction "VDD_141") (pintype "power_in"))
      (node (ref "J25") (pin "142") (pinfunction "VDD_142") (pintype "power_in"))
      (node (ref "J25") (pin "147") (pinfunction "VDD_147") (pintype "power_in"))
      (node (ref "J25") (pin "148") (pinfunction "VDD_148") (pintype "power_in"))
      (node (ref "J25") (pin "153") (pinfunction "VDD_153") (pintype "power_in"))
      (node (ref "J25") (pin "154") (pinfunction "VDD_154") (pintype "power_in"))
      (node (ref "J25") (pin "159") (pinfunction "VDD_159") (pintype "power_in"))
      (node (ref "J25") (pin "160") (pinfunction "VDD_160") (pintype "power_in"))
      (node (ref "J25") (pin "163") (pinfunction "VDD_163") (pintype "power_in"))
      (node (ref "R247") (pin "2") (pinfunction "2_2") (pintype "passive"))
      (node (ref "R253") (pin "2") (pinfunction "2_2") (pintype "passive"))
      (node (ref "R254") (pin "2") (pinfunction "2_2") (pintype "passive"))
      (node (ref "R255") (pin "2") (pinfunction "2_2") (pintype "passive"))
    )
    (net (code "145") (name "DDR4_VDDSPD_2V5") (class "Default")
      (node (ref "C326") (pin "2") (pinfunction "2_2") (pintype "passive"))
      (node (ref "J25") (pin "255") (pinfunction "VDDSPD_255") (pintype "power_in"))
    )
    (net (code "146") (name "GND") (class "Default")
      (node (ref "C320") (pin "1") (pinfunction "1_1") (pintype "passive"))
      (node (ref "C321") (pin "1") (pinfunction "1_1") (pintype "passive"))
      (node (ref "C322") (pin "1") (pinfunction "1_1") (pintype "passive"))
      (node (ref "C323") (pin "1") (pinfunction "1_1") (pintype "passive"))
      (node (ref "C324") (pin "1") (pinfunction "1_1") (pintype "passive"))
      (node (ref "C325") (pin "1") (pinfunction "1_1") (pintype "passive"))
      (node (ref "C326") (pin "1") (pinfunction "1_1") (pintype "passive"))
      (node (ref "C327") (pin "1") (pinfunction "1_1") (pintype "passive"))
      (node (ref "C328") (pin "1") (pinfunction "1_1") (pintype "passive"))
      (node (ref "C329") (pin "1") (pinfunction "1_1") (pintype "passive"))
      (node (ref "C330") (pin "1") (pinfunction "1_1") (pintype "passive"))
      (node (ref "C331") (pin "1") (pinfunction "1_1") (pintype "passive"))
      (node (ref "C332") (pin "1") (pinfunction "1_1") (pintype "passive"))
      (node (ref "C333") (pin "1") (pinfunction "1_1") (pintype "passive"))
      (node (ref "C334") (pin "1") (pinfunction "1_1") (pintype "passive"))
      (node (ref "C335") (pin "1") (pinfunction "1_1") (pintype "passive"))
      (node (ref "C336") (pin "1") (pinfunction "1_1") (pintype "passive"))
      (node (ref "C337") (pin "1") (pinfunction "1_1") (pintype "passive"))
      (node (ref "J25") (pin "1") (pinfunction "VSS_1") (pintype "power_in"))
      (node (ref "J25") (pin "10") (pinfunction "VSS_10") (pintype "power_in"))
      (node (ref "J25") (pin "102") (pinfunction "VSS_102") (pintype "power_in"))
      (node (ref "J25") (pin "103") (pinfunction "VSS_103") (pintype "power_in"))
      (node (ref "J25") (pin "106") (pinfunction "VSS_106") (pintype "power_in"))
      (node (ref "J25") (pin "107") (pinfunction "VSS_107") (pintype "power_in"))
      (node (ref "J25") (pin "14") (pinfunction "VSS_14") (pintype "power_in"))
      (node (ref "J25") (pin "15") (pinfunction "VSS_15") (pintype "power_in"))
      (node (ref "J25") (pin "167") (pinfunction "VSS_167") (pintype "power_in"))
      (node (ref "J25") (pin "168") (pinfunction "VSS_168") (pintype "power_in"))
      (node (ref "J25") (pin "171") (pinfunction "VSS_171") (pintype "power_in"))
      (node (ref "J25") (pin "172") (pinfunction "VSS_172") (pintype "power_in"))
      (node (ref "J25") (pin "175") (pinfunction "VSS_175") (pintype "power_in"))
      (node (ref "J25") (pin "176") (pinfunction "VSS_176") (pintype "power_in"))
      (node (ref "J25") (pin "18") (pinfunction "VSS_18") (pintype "power_in"))
      (node (ref "J25") (pin "180") (pinfunction "VSS_180") (pintype "power_in"))
      (node (ref "J25") (pin "181") (pinfunction "VSS_181") (pintype "power_in"))
      (node (ref "J25") (pin "184") (pinfunction "VSS_184") (pintype "power_in"))
      (node (ref "J25") (pin "185") (pinfunction "VSS_185") (pintype "power_in"))
      (node (ref "J25") (pin "188") (pinfunction "VSS_188") (pintype "power_in"))
      (node (ref "J25") (pin "189") (pinfunction "VSS_189") (pintype "power_in"))
      (node (ref "J25") (pin "19") (pinfunction "VSS_19") (pintype "power_in"))
      (node (ref "J25") (pin "192") (pinfunction "VSS_192") (pintype "power_in"))
      (node (ref "J25") (pin "193") (pinfunction "VSS_193") (pintype "power_in"))
      (node (ref "J25") (pin "196") (pinfunction "VSS_196") (pintype "power_in"))
      (node (ref "J25") (pin "197") (pinfunction "VSS_197") (pintype "power_in"))
      (node (ref "J25") (pin "2") (pinfunction "VSS_2") (pintype "power_in"))
      (node (ref "J25") (pin "201") (pinfunction "VSS_201") (pintype "power_in"))
      (node (ref "J25") (pin "202") (pinfunction "VSS_202") (pintype "power_in"))
      (node (ref "J25") (pin "205") (pinfunction "VSS_205") (pintype "power_in"))
      (node (ref "J25") (pin "206") (pinfunction "VSS_206") (pintype "power_in"))
      (node (ref "J25") (pin "209") (pinfunction "VSS_209") (pintype "power_in"))
      (node (ref "J25") (pin "210") (pinfunction "VSS_210") (pintype "power_in"))
      (node (ref "J25") (pin "213") (pinfunction "VSS_213") (pintype "power_in"))
      (node (ref "J25") (pin "214") (pinfunction "VSS_214") (pintype "power_in"))
      (node (ref "J25") (pin "217") (pinfunction "VSS_217") (pintype "power_in"))
      (node (ref "J25") (pin "218") (pinfunction "VSS_218") (pintype "power_in"))
      (node (ref "J25") (pin "22") (pinfunction "VSS_22") (pintype "power_in"))
      (node (ref "J25") (pin "222") (pinfunction "VSS_222") (pintype "power_in"))
      (node (ref "J25") (pin "223") (pinfunction "VSS_223") (pintype "power_in"))
      (node (ref "J25") (pin "226") (pinfunction "VSS_226") (pintype "power_in"))
      (node (ref "J25") (pin "227") (pinfunction "VSS_227") (pintype "power_in"))
      (node (ref "J25") (pin "23") (pinfunction "VSS_23") (pintype "power_in"))
      (node (ref "J25") (pin "230") (pinfunction "VSS_230") (pintype "power_in"))
      (node (ref "J25") (pin "231") (pinfunction "VSS_231") (pintype "power_in"))
      (node (ref "J25") (pin "234") (pinfunction "VSS_234") (pintype "power_in"))
      (node (ref "J25") (pin "235") (pinfunction "VSS_235") (pintype "power_in"))
      (node (ref "J25") (pin "238") (pinfunction "VSS_238") (pintype "power_in"))
      (node (ref "J25") (pin "239") (pinfunction "VSS_239") (pintype "power_in"))
      (node (ref "J25") (pin "243") (pinfunction "VSS_243") (pintype "power_in"))
      (node (ref "J25") (pin "244") (pinfunction "VSS_244") (pintype "power_in"))
      (node (ref "J25") (pin "247") (pinfunction "VSS_247") (pintype "power_in"))
      (node (ref "J25") (pin "248") (pinfunction "VSS_248") (pintype "power_in"))
      (node (ref "J25") (pin "251") (pinfunction "VSS_251") (pintype "power_in"))
      (node (ref "J25") (pin "252") (pinfunction "VSS_252") (pintype "power_in"))
      (node (ref "J25") (pin "26") (pinfunction "VSS_26") (pintype "power_in"))
      (node (ref "J25") (pin "27") (pinfunction "VSS_27") (pintype "power_in"))
      (node (ref "J25") (pin "30") (pinfunction "VSS_30") (pintype "power_in"))
      (node (ref "J25") (pin "31") (pinfunction "VSS_31") (pintype "power_in"))
      (node (ref "J25") (pin "35") (pinfunction "VSS_35") (pintype "power_in"))
      (node (ref "J25") (pin "36") (pinfunction "VSS_36") (pintype "power_in"))
      (node (ref "J25") (pin "39") (pinfunction "VSS_39") (pintype "power_in"))
      (node (ref "J25") (pin "40") (pinfunction "VSS_40") (pintype "power_in"))
      (node (ref "J25") (pin "43") (pinfunction "VSS_43") (pintype "power_in"))
      (node (ref "J25") (pin "44") (pinfunction "VSS_44") (pintype "power_in"))
      (node (ref "J25") (pin "47") (pinfunction "VSS_47") (pintype "power_in"))
      (node (ref "J25") (pin "48") (pinfunction "VSS_48") (pintype "power_in"))
      (node (ref "J25") (pin "5") (pinfunction "VSS_5") (pintype "power_in"))
      (node (ref "J25") (pin "51") (pinfunction "VSS_51") (pintype "power_in"))
      (node (ref "J25") (pin "52") (pinfunction "VSS_52") (pintype "power_in"))
      (node (ref "J25") (pin "56") (pinfunction "VSS_56") (pintype "power_in"))
      (node (ref "J25") (pin "57") (pinfunction "VSS_57") (pintype "power_in"))
      (node (ref "J25") (pin "6") (pinfunction "VSS_6") (pintype "power_in"))
      (node (ref "J25") (pin "60") (pinfunction "VSS_60") (pintype "power_in"))
      (node (ref "J25") (pin "61") (pinfunction "VSS_61") (pintype "power_in"))
      (node (ref "J25") (pin "64") (pinfunction "VSS_64") (pintype "power_in"))
      (node (ref "J25") (pin "65") (pinfunction "VSS_65") (pintype "power_in"))
      (node (ref "J25") (pin "68") (pinfunction "VSS_68") (pintype "power_in"))
      (node (ref "J25") (pin "69") (pinfunction "VSS_69") (pintype "power_in"))
      (node (ref "J25") (pin "72") (pinfunction "VSS_72") (pintype "power_in"))
      (node (ref "J25") (pin "73") (pinfunction "VSS_73") (pintype "power_in"))
      (node (ref "J25") (pin "77") (pinfunction "VSS_77") (pintype "power_in"))
      (node (ref "J25") (pin "78") (pinfunction "VSS_78") (pintype "power_in"))
      (node (ref "J25") (pin "81") (pinfunction "VSS_81") (pintype "power_in"))
      (node (ref "J25") (pin "82") (pinfunction "VSS_82") (pintype "power_in"))
      (node (ref "J25") (pin "85") (pinfunction "VSS_85") (pintype "power_in"))
      (node (ref "J25") (pin "86") (pinfunction "VSS_86") (pintype "power_in"))
      (node (ref "J25") (pin "89") (pinfunction "VSS_89") (pintype "power_in"))
      (node (ref "J25") (pin "9") (pinfunction "VSS_9") (pintype "power_in"))
      (node (ref "J25") (pin "90") (pinfunction "VSS_90") (pintype "power_in"))
      (node (ref "J25") (pin "93") (pinfunction "VSS_93") (pintype "power_in"))
      (node (ref "J25") (pin "94") (pinfunction "VSS_94") (pintype "power_in"))
      (node (ref "J25") (pin "98") (pinfunction "VSS_98") (pintype "power_in"))
      (node (ref "J25") (pin "99") (pinfunction "VSS_99") (pintype "power_in"))
      (node (ref "R248") (pin "2") (pinfunction "2_2") (pintype "passive"))
      (node (ref "R249") (pin "2") (pinfunction "2_2") (pintype "passive"))
      (node (ref "R250") (pin "2") (pinfunction "2_2") (pintype "passive"))
      (node (ref "R251") (pin "2") (pinfunction "2_2") (pintype "passive"))
      (node (ref "R252") (pin "2") (pinfunction "2_2") (pintype "passive"))
      (node (ref "R256") (pin "1") (pinfunction "1_1") (pintype "passive"))
    )
    (net (code "147") (name "PL_DDR4_VPP_2V5") (class "Default")
      (node (ref "J25") (pin "257") (pinfunction "VPP_257") (pintype "power_in"))
      (node (ref "J25") (pin "259") (pinfunction "VPP_259") (pintype "power_in"))
    )
    (net (code "148") (name "PL_DDR4_VTT") (class "Default")
      (node (ref "J25") (pin "258") (pinfunction "VTT_258") (pintype "power_in"))
    )
  )
)
